# CircMordaza.net
KiCad netlist of a schematic drawn in EAGLE
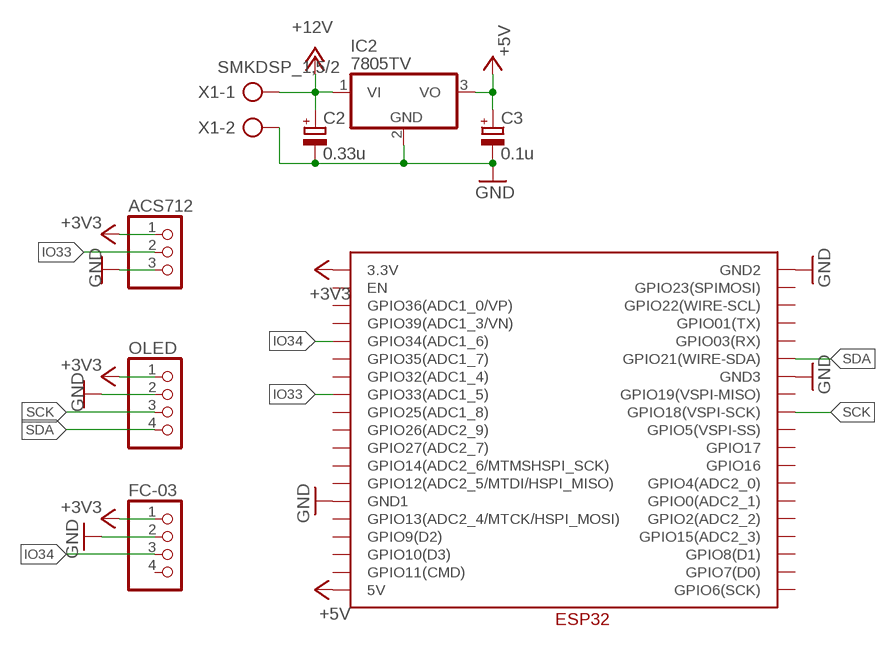
[diagram p0: schematic, sheet 1]

(export (version "E")
  (design (tool "Eeschema 10.0.6"))
  (components
    (comp (ref "ACS712")
      (value "PINHD-1X3")
      (footprint "eagle-import:1X03")
      (libsource (lib "eagle-import") (part "PINHD-1X3"))
    )
    (comp (ref "C2")
      (value "0.33u")
      (footprint "eagle-import:TT2D6")
      (libsource (lib "eagle-import") (part "CPOL-EUTT2D6"))
    )
    (comp (ref "C3")
      (value "0.1u")
      (footprint "eagle-import:TT2D6")
      (libsource (lib "eagle-import") (part "CPOL-EUTT2D6"))
    )
    (comp (ref "FC-03")
      (value "PINHD-1X4")
      (footprint "eagle-import:1X04")
      (libsource (lib "eagle-import") (part "PINHD-1X4"))
    )
    (comp (ref "IC2")
      (value "7805TV")
      (footprint "eagle-import:TO220V")
      (libsource (lib "eagle-import") (part "78TV05"))
    )
    (comp (ref "OLED")
      (value "PINHD-1X4")
      (footprint "eagle-import:1X04")
      (libsource (lib "eagle-import") (part "PINHD-1X4"))
    )
    (comp (ref "U$1")
      (value "ESP32WESP32W")
      (footprint "eagle-import:ESP32W")
      (libsource (lib "eagle-import") (part "ESP32WESP32W"))
    )
    (comp (ref "X1")
      (value "SMKDSP_1,5/2")
      (footprint "eagle-import:SMKDSP_1,5_2")
      (fields (field (name "MF") "FARNELL") (field (name "MPN") "1733570"))
      (libsource (lib "eagle-import") (part "SMKDSP_1,5/2"))
    )
  )
  (nets
    (net (code "1") (name "+3V3") (class "Default")
      (node (ref "ACS712") (pin "1") (pinfunction "1_1") (pintype "passive"))
      (node (ref "FC-03") (pin "1") (pinfunction "1_1") (pintype "passive"))
      (node (ref "OLED") (pin "1") (pinfunction "1_1") (pintype "passive"))
      (node (ref "U$1") (pin "3.3V") (pinfunction "3.3V_3.3V") (pintype "bidirectional"))
    )
    (net (code "2") (name "+5V") (class "Default")
      (node (ref "C3") (pin "+") (pinfunction "+_+") (pintype "passive"))
      (node (ref "IC2") (pin "3") (pinfunction "VO_3") (pintype "passive"))
      (node (ref "U$1") (pin "5V") (pinfunction "5V_5V") (pintype "bidirectional"))
    )
    (net (code "3") (name "+12V") (class "Default")
      (node (ref "C2") (pin "+") (pinfunction "+_+") (pintype "passive"))
      (node (ref "IC2") (pin "1") (pinfunction "VI_1") (pintype "input"))
      (node (ref "X1") (pin "1") (pinfunction "KL_1") (pintype "passive"))
    )
    (net (code "4") (name "GND") (class "Default")
      (node (ref "ACS712") (pin "3") (pinfunction "3_3") (pintype "passive"))
      (node (ref "C2") (pin "-") (pinfunction "-_-") (pintype "passive"))
      (node (ref "C3") (pin "-") (pinfunction "-_-") (pintype "passive"))
      (node (ref "FC-03") (pin "2") (pinfunction "2_2") (pintype "passive"))
      (node (ref "IC2") (pin "2") (pinfunction "GND_2") (pintype "passive"))
      (node (ref "OLED") (pin "2") (pinfunction "2_2") (pintype "passive"))
      (node (ref "U$1") (pin "GND1") (pinfunction "GND1_GND1") (pintype "bidirectional"))
      (node (ref "U$1") (pin "GND2") (pinfunction "GND2_GND2") (pintype "bidirectional"))
      (node (ref "U$1") (pin "GND3") (pinfunction "GND3_GND3") (pintype "bidirectional"))
      (node (ref "X1") (pin "2") (pinfunction "KL_2") (pintype "passive"))
    )
    (net (code "5") (name "IO33") (class "Default")
      (node (ref "ACS712") (pin "2") (pinfunction "2_2") (pintype "passive"))
      (node (ref "U$1") (pin "GPIO33") (pinfunction "GPIO33(ADC1_5)_GPIO33") (pintype "bidirectional"))
    )
    (net (code "6") (name "IO34") (class "Default")
      (node (ref "FC-03") (pin "3") (pinfunction "3_3") (pintype "passive"))
      (node (ref "U$1") (pin "GPIO34") (pinfunction "GPIO34(ADC1_6)_GPIO34") (pintype "bidirectional"))
    )
    (net (code "7") (name "SCK") (class "Default")
      (node (ref "OLED") (pin "3") (pinfunction "3_3") (pintype "passive"))
      (node (ref "U$1") (pin "GPIO18") (pinfunction "GPIO18(VSPI-SCK)_GPIO18") (pintype "bidirectional"))
    )
    (net (code "8") (name "SDA") (class "Default")
      (node (ref "OLED") (pin "4") (pinfunction "4_4") (pintype "passive"))
      (node (ref "U$1") (pin "GPIO21") (pinfunction "GPIO21(WIRE-SDA)_GPIO21") (pintype "bidirectional"))
    )
    (net (code "9") (name "unconnected-(FC-03-Pad4)") (class "Default")
      (node (ref "FC-03") (pin "4") (pinfunction "4_4") (pintype "passive"))
    )
    (net (code "10") (name "unconnected-(U$1-GPIO0(ADC2_1)-PadGPIO0)") (class "Default")
      (node (ref "U$1") (pin "GPIO0") (pinfunction "GPIO0(ADC2_1)_GPIO0") (pintype "bidirectional"))
    )
    (net (code "11") (name "unconnected-(U$1-GPIO01(TX)-PadTX)") (class "Default")
      (node (ref "U$1") (pin "TX") (pinfunction "GPIO01(TX)_TX") (pintype "bidirectional"))
    )
    (net (code "12") (name "unconnected-(U$1-GPIO2(ADC2_2)-PadGPIO2)") (class "Default")
      (node (ref "U$1") (pin "GPIO2") (pinfunction "GPIO2(ADC2_2)_GPIO2") (pintype "bidirectional"))
    )
    (net (code "13") (name "unconnected-(U$1-GPIO03(RX)-PadRX)") (class "Default")
      (node (ref "U$1") (pin "RX") (pinfunction "GPIO03(RX)_RX") (pintype "bidirectional"))
    )
    (net (code "14") (name "unconnected-(U$1-GPIO4(ADC2_0)-PadGPIO4)") (class "Default")
      (node (ref "U$1") (pin "GPIO4") (pinfunction "GPIO4(ADC2_0)_GPIO4") (pintype "bidirectional"))
    )
    (net (code "15") (name "unconnected-(U$1-GPIO5(VSPI-SS)-PadGPIO5)") (class "Default")
      (node (ref "U$1") (pin "GPIO5") (pinfunction "GPIO5(VSPI-SS)_GPIO5") (pintype "bidirectional"))
    )
    (net (code "16") (name "unconnected-(U$1-GPIO6(SCK)-PadCLK)") (class "Default")
      (node (ref "U$1") (pin "CLK") (pinfunction "GPIO6(SCK)_CLK") (pintype "bidirectional"))
    )
    (net (code "17") (name "unconnected-(U$1-GPIO7(D0)-PadSDO)") (class "Default")
      (node (ref "U$1") (pin "SDO") (pinfunction "GPIO7(D0)_SDO") (pintype "bidirectional"))
    )
    (net (code "18") (name "unconnected-(U$1-GPIO8(D1)-PadSDI)") (class "Default")
      (node (ref "U$1") (pin "SDI") (pinfunction "GPIO8(D1)_SDI") (pintype "bidirectional"))
    )
    (net (code "19") (name "unconnected-(U$1-GPIO9(D2)-PadD2)") (class "Default")
      (node (ref "U$1") (pin "D2") (pinfunction "GPIO9(D2)_D2") (pintype "bidirectional"))
    )
    (net (code "20") (name "unconnected-(U$1-GPIO10(D3)-PadD3)") (class "Default")
      (node (ref "U$1") (pin "D3") (pinfunction "GPIO10(D3)_D3") (pintype "bidirectional"))
    )
    (net (code "21") (name "unconnected-(U$1-GPIO11(CMD)-PadCMD)") (class "Default")
      (node (ref "U$1") (pin "CMD") (pinfunction "GPIO11(CMD)_CMD") (pintype "bidirectional"))
    )
    (net (code "22") (name "unconnected-(U$1-GPIO12(ADC2_5{slash}MTDI{slash}HSPI_MISO)-PadGPIO12)") (class "Default")
      (node (ref "U$1") (pin "GPIO12") (pinfunction "GPIO12(ADC2_5/MTDI/HSPI_MISO)_GPIO12") (pintype "bidirectional"))
    )
    (net (code "23") (name "unconnected-(U$1-GPIO13(ADC2_4{slash}MTCK{slash}HSPI_MOSI)-PadGPIO13)") (class "Default")
      (node (ref "U$1") (pin "GPIO13") (pinfunction "GPIO13(ADC2_4/MTCK/HSPI_MOSI)_GPIO13") (pintype "bidirectional"))
    )
    (net (code "24") (name "unconnected-(U$1-GPIO14(ADC2_6{slash}MTMSHSPI_SCK)-PadGPIO14)") (class "Default")
      (node (ref "U$1") (pin "GPIO14") (pinfunction "GPIO14(ADC2_6/MTMSHSPI_SCK)_GPIO14") (pintype "bidirectional"))
    )
    (net (code "25") (name "unconnected-(U$1-GPIO15(ADC2_3)-PadGPIO15)") (class "Default")
      (node (ref "U$1") (pin "GPIO15") (pinfunction "GPIO15(ADC2_3)_GPIO15") (pintype "bidirectional"))
    )
    (net (code "26") (name "unconnected-(U$1-GPIO19(VSPI-MISO)-PadGPIO19)") (class "Default")
      (node (ref "U$1") (pin "GPIO19") (pinfunction "GPIO19(VSPI-MISO)_GPIO19") (pintype "bidirectional"))
    )
    (net (code "27") (name "unconnected-(U$1-GPIO22(WIRE-SCL)-PadGPIO22)") (class "Default")
      (node (ref "U$1") (pin "GPIO22") (pinfunction "GPIO22(WIRE-SCL)_GPIO22") (pintype "bidirectional"))
    )
    (net (code "28") (name "unconnected-(U$1-GPIO23(SPIMOSI)-PadGPIO23)") (class "Default")
      (node (ref "U$1") (pin "GPIO23") (pinfunction "GPIO23(SPIMOSI)_GPIO23") (pintype "bidirectional"))
    )
    (net (code "29") (name "unconnected-(U$1-GPIO25(ADC1_8)-PadGPIO25)") (class "Default")
      (node (ref "U$1") (pin "GPIO25") (pinfunction "GPIO25(ADC1_8)_GPIO25") (pintype "bidirectional"))
    )
    (net (code "30") (name "unconnected-(U$1-GPIO26(ADC2_9)-PadGPIO26)") (class "Default")
      (node (ref "U$1") (pin "GPIO26") (pinfunction "GPIO26(ADC2_9)_GPIO26") (pintype "bidirectional"))
    )
    (net (code "31") (name "unconnected-(U$1-GPIO27(ADC2_7)-PadGPIO27)") (class "Default")
      (node (ref "U$1") (pin "GPIO27") (pinfunction "GPIO27(ADC2_7)_GPIO27") (pintype "bidirectional"))
    )
    (net (code "32") (name "unconnected-(U$1-GPIO32(ADC1_4)-PadGPIO32)") (class "Default")
      (node (ref "U$1") (pin "GPIO32") (pinfunction "GPIO32(ADC1_4)_GPIO32") (pintype "bidirectional"))
    )
    (net (code "33") (name "unconnected-(U$1-GPIO35(ADC1_7)-PadGPIO35)") (class "Default")
      (node (ref "U$1") (pin "GPIO35") (pinfunction "GPIO35(ADC1_7)_GPIO35") (pintype "bidirectional"))
    )
    (net (code "34") (name "unconnected-(U$1-GPIO36(ADC1_0{slash}VP)-PadVP)") (class "Default")
      (node (ref "U$1") (pin "VP") (pinfunction "GPIO36(ADC1_0/VP)_VP") (pintype "bidirectional"))
    )
    (net (code "35") (name "unconnected-(U$1-GPIO39(ADC1_3{slash}VN)-PadVN)") (class "Default")
      (node (ref "U$1") (pin "VN") (pinfunction "GPIO39(ADC1_3/VN)_VN") (pintype "bidirectional"))
    )
    (net (code "36") (name "unconnected-(U$1-PadEN)") (class "Default")
      (node (ref "U$1") (pin "EN") (pinfunction "EN_EN") (pintype "bidirectional"))
    )
    (net (code "37") (name "unconnected-(U$1-PadGPIO16)") (class "Default")
      (node (ref "U$1") (pin "GPIO16") (pinfunction "GPIO16_GPIO16") (pintype "bidirectional"))
    )
    (net (code "38") (name "unconnected-(U$1-PadGPIO17)") (class "Default")
      (node (ref "U$1") (pin "GPIO17") (pinfunction "GPIO17_GPIO17") (pintype "bidirectional"))
    )
  )
)
